# 2_Motors.net
KiCad netlist of a schematic drawn in EAGLE
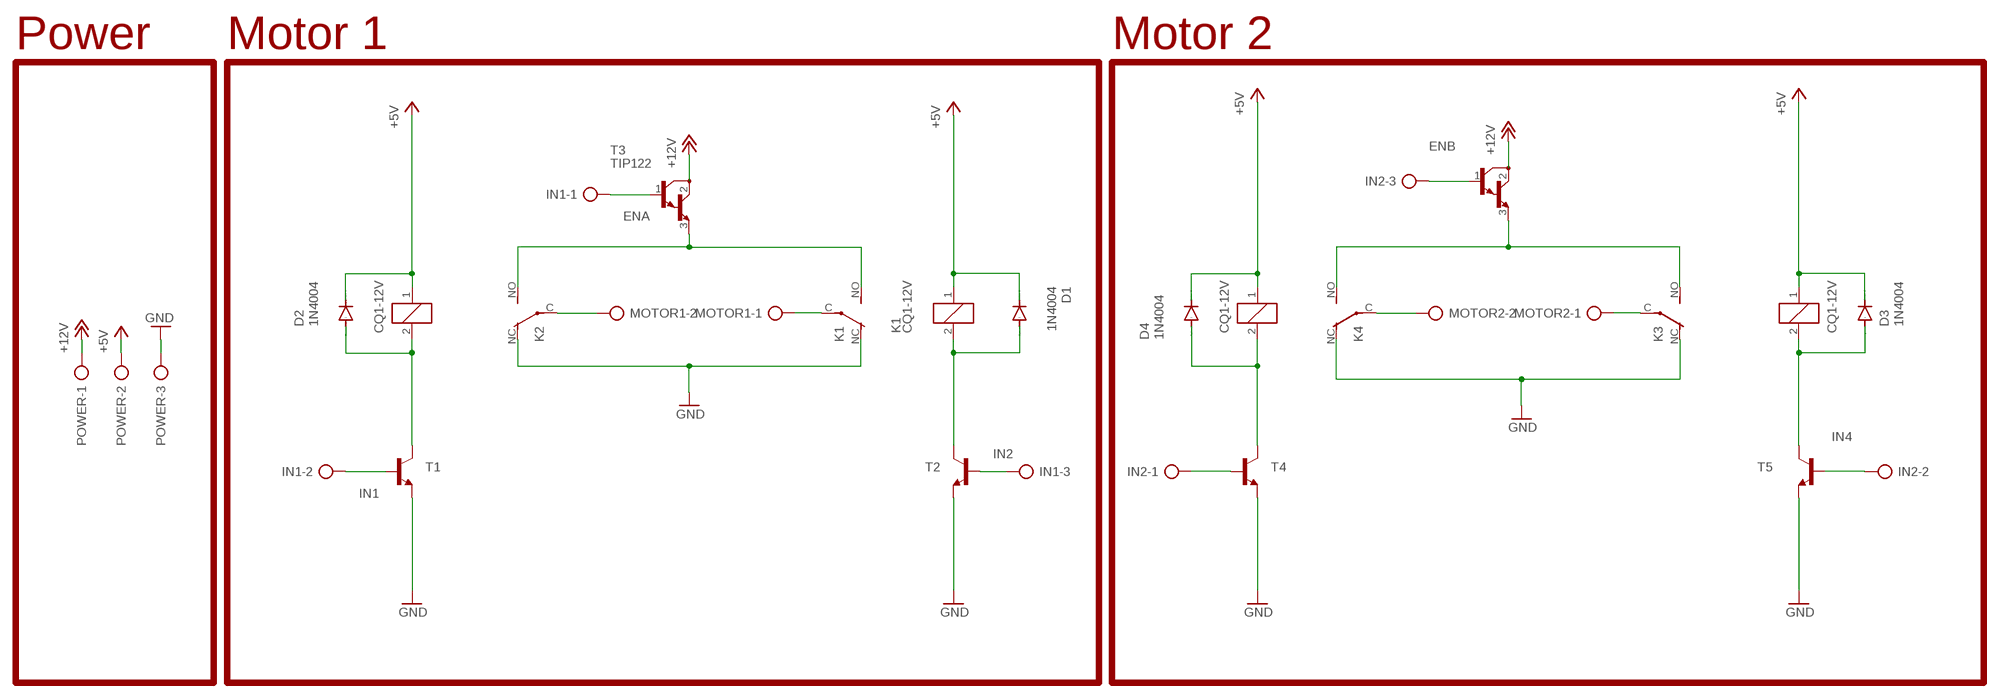
[diagram p0: schematic, sheet 1]

(export (version "E")
  (design (tool "Eeschema 10.0.6"))
  (components
    (comp (ref "D1")
      (value "1N4004")
      (footprint "eagle-import:DO41-10")
      (libsource (lib "eagle-import") (part "1N4004"))
    )
    (comp (ref "D2")
      (value "1N4004")
      (footprint "eagle-import:DO41-10")
      (libsource (lib "eagle-import") (part "1N4004"))
    )
    (comp (ref "D3")
      (value "1N4004")
      (footprint "eagle-import:DO41-10")
      (libsource (lib "eagle-import") (part "1N4004"))
    )
    (comp (ref "D4")
      (value "1N4004")
      (footprint "eagle-import:DO41-10")
      (libsource (lib "eagle-import") (part "1N4004"))
    )
    (comp (ref "IN1")
      (value "AK300/3")
      (footprint "eagle-import:AK300_3")
      (libsource (lib "eagle-import") (part "AK300/3"))
    )
    (comp (ref "IN2")
      (value "AK300/3")
      (footprint "eagle-import:AK300_3")
      (libsource (lib "eagle-import") (part "AK300/3"))
    )
    (comp (ref "K1")
      (value "CQ1-12V")
      (footprint "eagle-import:CQ1")
      (libsource (lib "eagle-import") (part "CQ1-12V"))
    )
    (comp (ref "K2")
      (value "CQ1-12V")
      (footprint "eagle-import:CQ1")
      (libsource (lib "eagle-import") (part "CQ1-12V"))
    )
    (comp (ref "K3")
      (value "CQ1-12V")
      (footprint "eagle-import:CQ1")
      (libsource (lib "eagle-import") (part "CQ1-12V"))
    )
    (comp (ref "K4")
      (value "CQ1-12V")
      (footprint "eagle-import:CQ1")
      (libsource (lib "eagle-import") (part "CQ1-12V"))
    )
    (comp (ref "MOTOR1")
      (value "AK300/2")
      (footprint "eagle-import:AK300_2")
      (libsource (lib "eagle-import") (part "AK300/2"))
    )
    (comp (ref "MOTOR2")
      (value "AK300/2")
      (footprint "eagle-import:AK300_2")
      (libsource (lib "eagle-import") (part "AK300/2"))
    )
    (comp (ref "POWER")
      (value "AK300/3")
      (footprint "eagle-import:AK300_3")
      (libsource (lib "eagle-import") (part "AK300/3"))
    )
    (comp (ref "T1")
      (value "2N2222-NPN-TO92-EBC")
      (footprint "eagle-import:TO92-EBC")
      (libsource (lib "eagle-import") (part "-NPN-TO92-EBC2N2222"))
    )
    (comp (ref "T2")
      (value "2N2222-NPN-TO92-EBC")
      (footprint "eagle-import:TO92-EBC")
      (libsource (lib "eagle-import") (part "-NPN-TO92-EBC2N2222"))
    )
    (comp (ref "T3")
      (value "TIP122")
      (footprint "eagle-import:TO220")
      (libsource (lib "eagle-import") (part "TIP122"))
    )
    (comp (ref "T4")
      (value "2N2222-NPN-TO92-EBC")
      (footprint "eagle-import:TO92-EBC")
      (libsource (lib "eagle-import") (part "-NPN-TO92-EBC2N2222"))
    )
    (comp (ref "T5")
      (value "2N2222-NPN-TO92-EBC")
      (footprint "eagle-import:TO92-EBC")
      (libsource (lib "eagle-import") (part "-NPN-TO92-EBC2N2222"))
    )
    (comp (ref "T6")
      (value "TIP122")
      (footprint "eagle-import:TO220")
      (libsource (lib "eagle-import") (part "TIP122"))
    )
  )
  (nets
    (net (code "1") (name "+5V") (class "Default")
      (node (ref "D1") (pin "C") (pinfunction "C_C") (pintype "passive"))
      (node (ref "D2") (pin "C") (pinfunction "C_C") (pintype "passive"))
      (node (ref "D3") (pin "C") (pinfunction "C_C") (pintype "passive"))
      (node (ref "D4") (pin "C") (pinfunction "C_C") (pintype "passive"))
      (node (ref "K1") (pin "1") (pinfunction "1_1") (pintype "passive"))
      (node (ref "K2") (pin "1") (pinfunction "1_1") (pintype "passive"))
      (node (ref "K3") (pin "1") (pinfunction "1_1") (pintype "passive"))
      (node (ref "K4") (pin "1") (pinfunction "1_1") (pintype "passive"))
      (node (ref "POWER") (pin "2") (pinfunction "KL_2") (pintype "passive"))
    )
    (net (code "2") (name "+12V") (class "Default")
      (node (ref "POWER") (pin "1") (pinfunction "KL_1") (pintype "passive"))
      (node (ref "T3") (pin "2") (pinfunction "C_2") (pintype "passive"))
      (node (ref "T6") (pin "2") (pinfunction "C_2") (pintype "passive"))
    )
    (net (code "3") (name "/ENA") (class "Default")
      (node (ref "IN1") (pin "1") (pinfunction "KL_1") (pintype "passive"))
      (node (ref "T3") (pin "1") (pinfunction "B_1") (pintype "passive"))
    )
    (net (code "4") (name "/ENB") (class "Default")
      (node (ref "IN2") (pin "3") (pinfunction "KL_3") (pintype "passive"))
      (node (ref "T6") (pin "1") (pinfunction "B_1") (pintype "passive"))
    )
    (net (code "5") (name "/IN1") (class "Default")
      (node (ref "IN1") (pin "2") (pinfunction "KL_2") (pintype "passive"))
      (node (ref "T1") (pin "B") (pinfunction "B_B") (pintype "passive"))
    )
    (net (code "6") (name "/IN2") (class "Default")
      (node (ref "IN1") (pin "3") (pinfunction "KL_3") (pintype "passive"))
      (node (ref "T2") (pin "B") (pinfunction "B_B") (pintype "passive"))
    )
    (net (code "7") (name "/IN4") (class "Default")
      (node (ref "IN2") (pin "2") (pinfunction "KL_2") (pintype "passive"))
      (node (ref "T5") (pin "B") (pinfunction "B_B") (pintype "passive"))
    )
    (net (code "8") (name "GND") (class "Default")
      (node (ref "K1") (pin "NC") (pinfunction "O_NC") (pintype "passive"))
      (node (ref "K2") (pin "NC") (pinfunction "O_NC") (pintype "passive"))
      (node (ref "K3") (pin "NC") (pinfunction "O_NC") (pintype "passive"))
      (node (ref "K4") (pin "NC") (pinfunction "O_NC") (pintype "passive"))
      (node (ref "POWER") (pin "3") (pinfunction "KL_3") (pintype "passive"))
      (node (ref "T1") (pin "E") (pinfunction "E_E") (pintype "passive"))
      (node (ref "T2") (pin "E") (pinfunction "E_E") (pintype "passive"))
      (node (ref "T4") (pin "E") (pinfunction "E_E") (pintype "passive"))
      (node (ref "T5") (pin "E") (pinfunction "E_E") (pintype "passive"))
    )
    (net (code "9") (name "Net-(D1-PadA)") (class "Default")
      (node (ref "D1") (pin "A") (pinfunction "A_A") (pintype "passive"))
      (node (ref "K1") (pin "2") (pinfunction "2_2") (pintype "passive"))
      (node (ref "T2") (pin "C") (pinfunction "C_C") (pintype "passive"))
    )
    (net (code "10") (name "Net-(D2-PadA)") (class "Default")
      (node (ref "D2") (pin "A") (pinfunction "A_A") (pintype "passive"))
      (node (ref "K2") (pin "2") (pinfunction "2_2") (pintype "passive"))
      (node (ref "T1") (pin "C") (pinfunction "C_C") (pintype "passive"))
    )
    (net (code "11") (name "Net-(D3-PadA)") (class "Default")
      (node (ref "D3") (pin "A") (pinfunction "A_A") (pintype "passive"))
      (node (ref "K3") (pin "2") (pinfunction "2_2") (pintype "passive"))
      (node (ref "T5") (pin "C") (pinfunction "C_C") (pintype "passive"))
    )
    (net (code "12") (name "Net-(D4-PadA)") (class "Default")
      (node (ref "D4") (pin "A") (pinfunction "A_A") (pintype "passive"))
      (node (ref "K4") (pin "2") (pinfunction "2_2") (pintype "passive"))
      (node (ref "T4") (pin "C") (pinfunction "C_C") (pintype "passive"))
    )
    (net (code "13") (name "Net-(IN2A-KL)") (class "Default")
      (node (ref "IN2") (pin "1") (pinfunction "KL_1") (pintype "passive"))
      (node (ref "T4") (pin "B") (pinfunction "B_B") (pintype "passive"))
    )
    (net (code "14") (name "Net-(K1B-P)") (class "Default")
      (node (ref "K1") (pin "C") (pinfunction "P_C") (pintype "passive"))
      (node (ref "MOTOR1") (pin "1") (pinfunction "KL_1") (pintype "passive"))
    )
    (net (code "15") (name "Net-(K1B-S)") (class "Default")
      (node (ref "K1") (pin "NO") (pinfunction "S_NO") (pintype "passive"))
      (node (ref "K2") (pin "NO") (pinfunction "S_NO") (pintype "passive"))
      (node (ref "T3") (pin "3") (pinfunction "E_3") (pintype "passive"))
    )
    (net (code "16") (name "Net-(K2B-P)") (class "Default")
      (node (ref "K2") (pin "C") (pinfunction "P_C") (pintype "passive"))
      (node (ref "MOTOR1") (pin "2") (pinfunction "KL_2") (pintype "passive"))
    )
    (net (code "17") (name "Net-(K3B-P)") (class "Default")
      (node (ref "K3") (pin "C") (pinfunction "P_C") (pintype "passive"))
      (node (ref "MOTOR2") (pin "1") (pinfunction "KL_1") (pintype "passive"))
    )
    (net (code "18") (name "Net-(K3B-S)") (class "Default")
      (node (ref "K3") (pin "NO") (pinfunction "S_NO") (pintype "passive"))
      (node (ref "K4") (pin "NO") (pinfunction "S_NO") (pintype "passive"))
      (node (ref "T6") (pin "3") (pinfunction "E_3") (pintype "passive"))
    )
    (net (code "19") (name "Net-(K4B-P)") (class "Default")
      (node (ref "K4") (pin "C") (pinfunction "P_C") (pintype "passive"))
      (node (ref "MOTOR2") (pin "2") (pinfunction "KL_2") (pintype "passive"))
    )
  )
)
